# geigerDC3.net
KiCad netlist of a schematic drawn in EAGLE
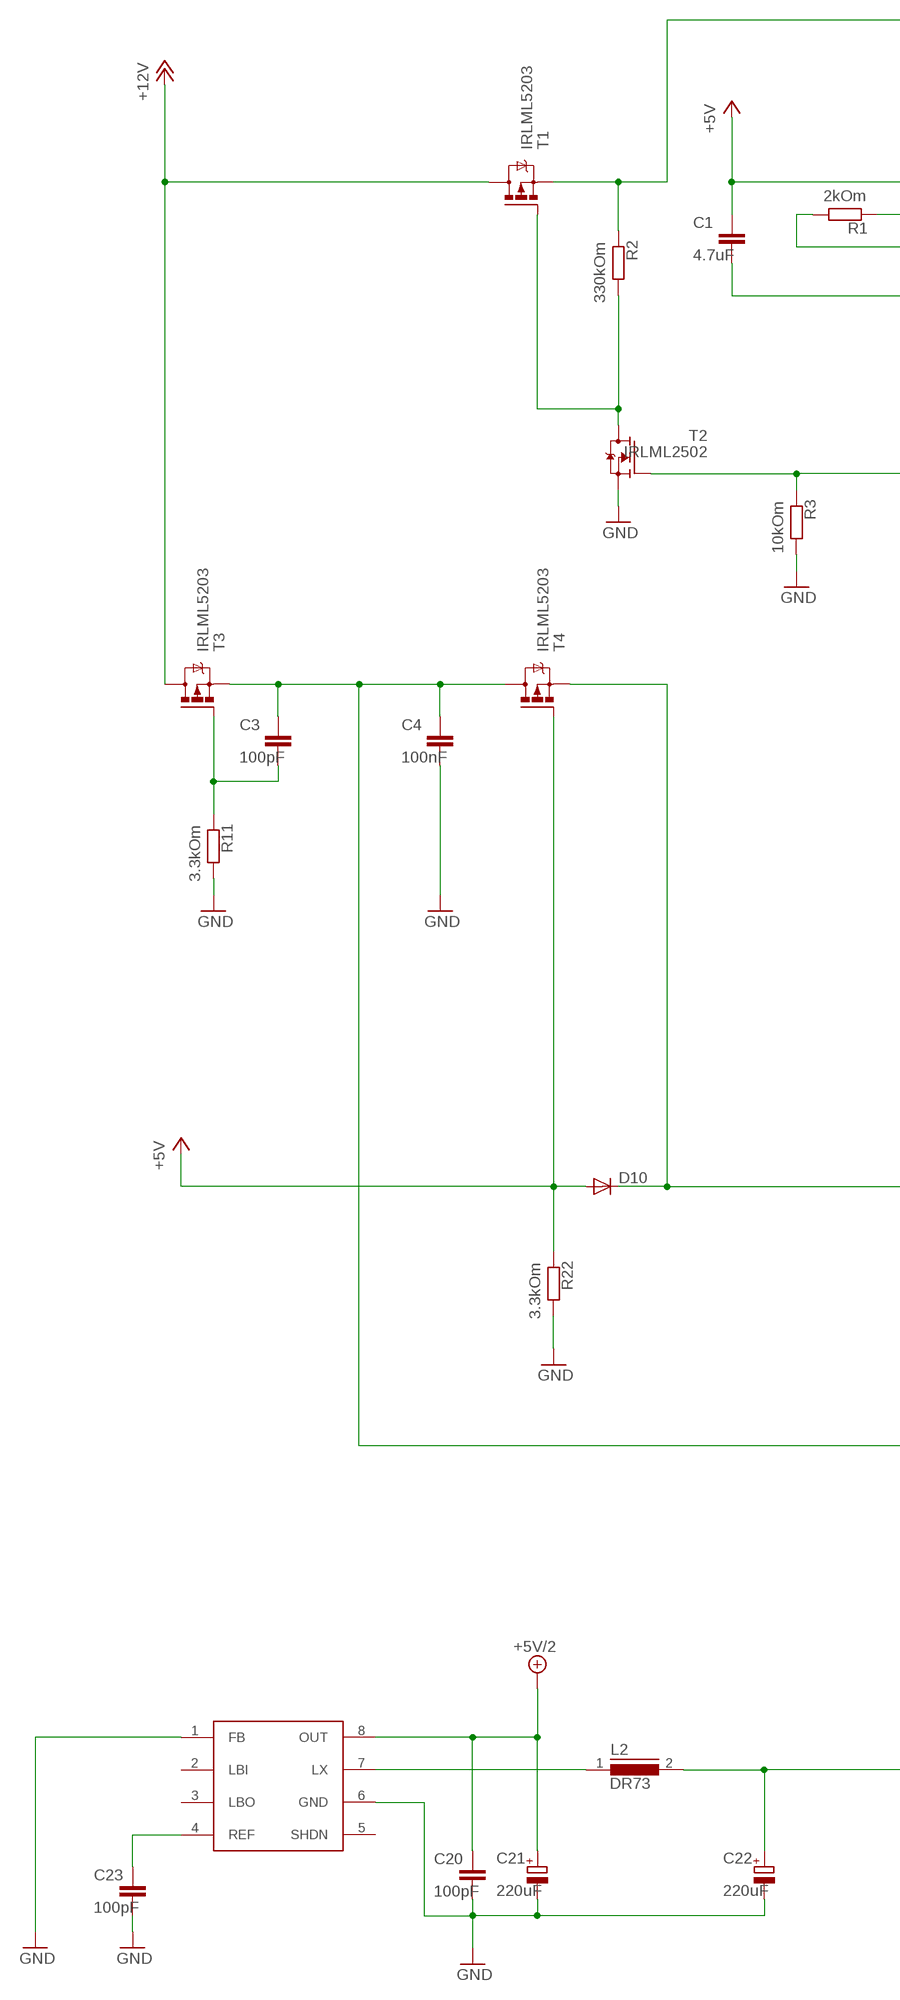
[diagram p0: schematic, sheet 1, part 1 of 3]
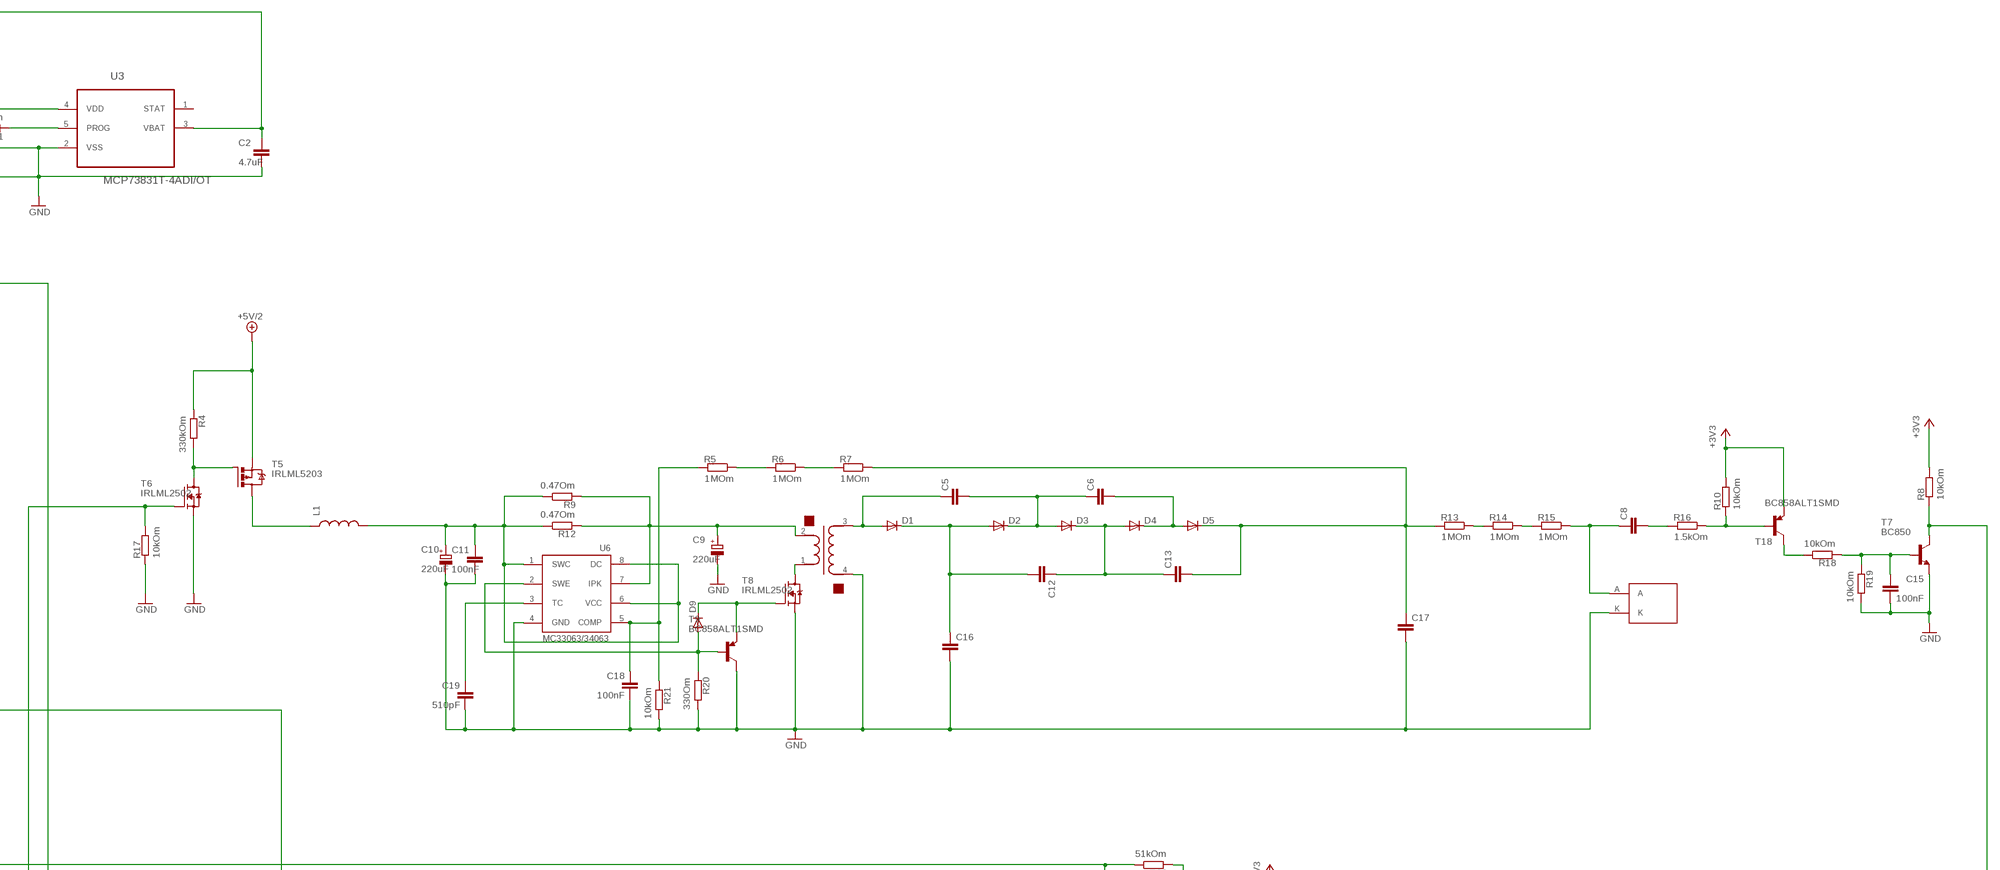
[diagram p1: schematic, sheet 1, part 2 of 3]
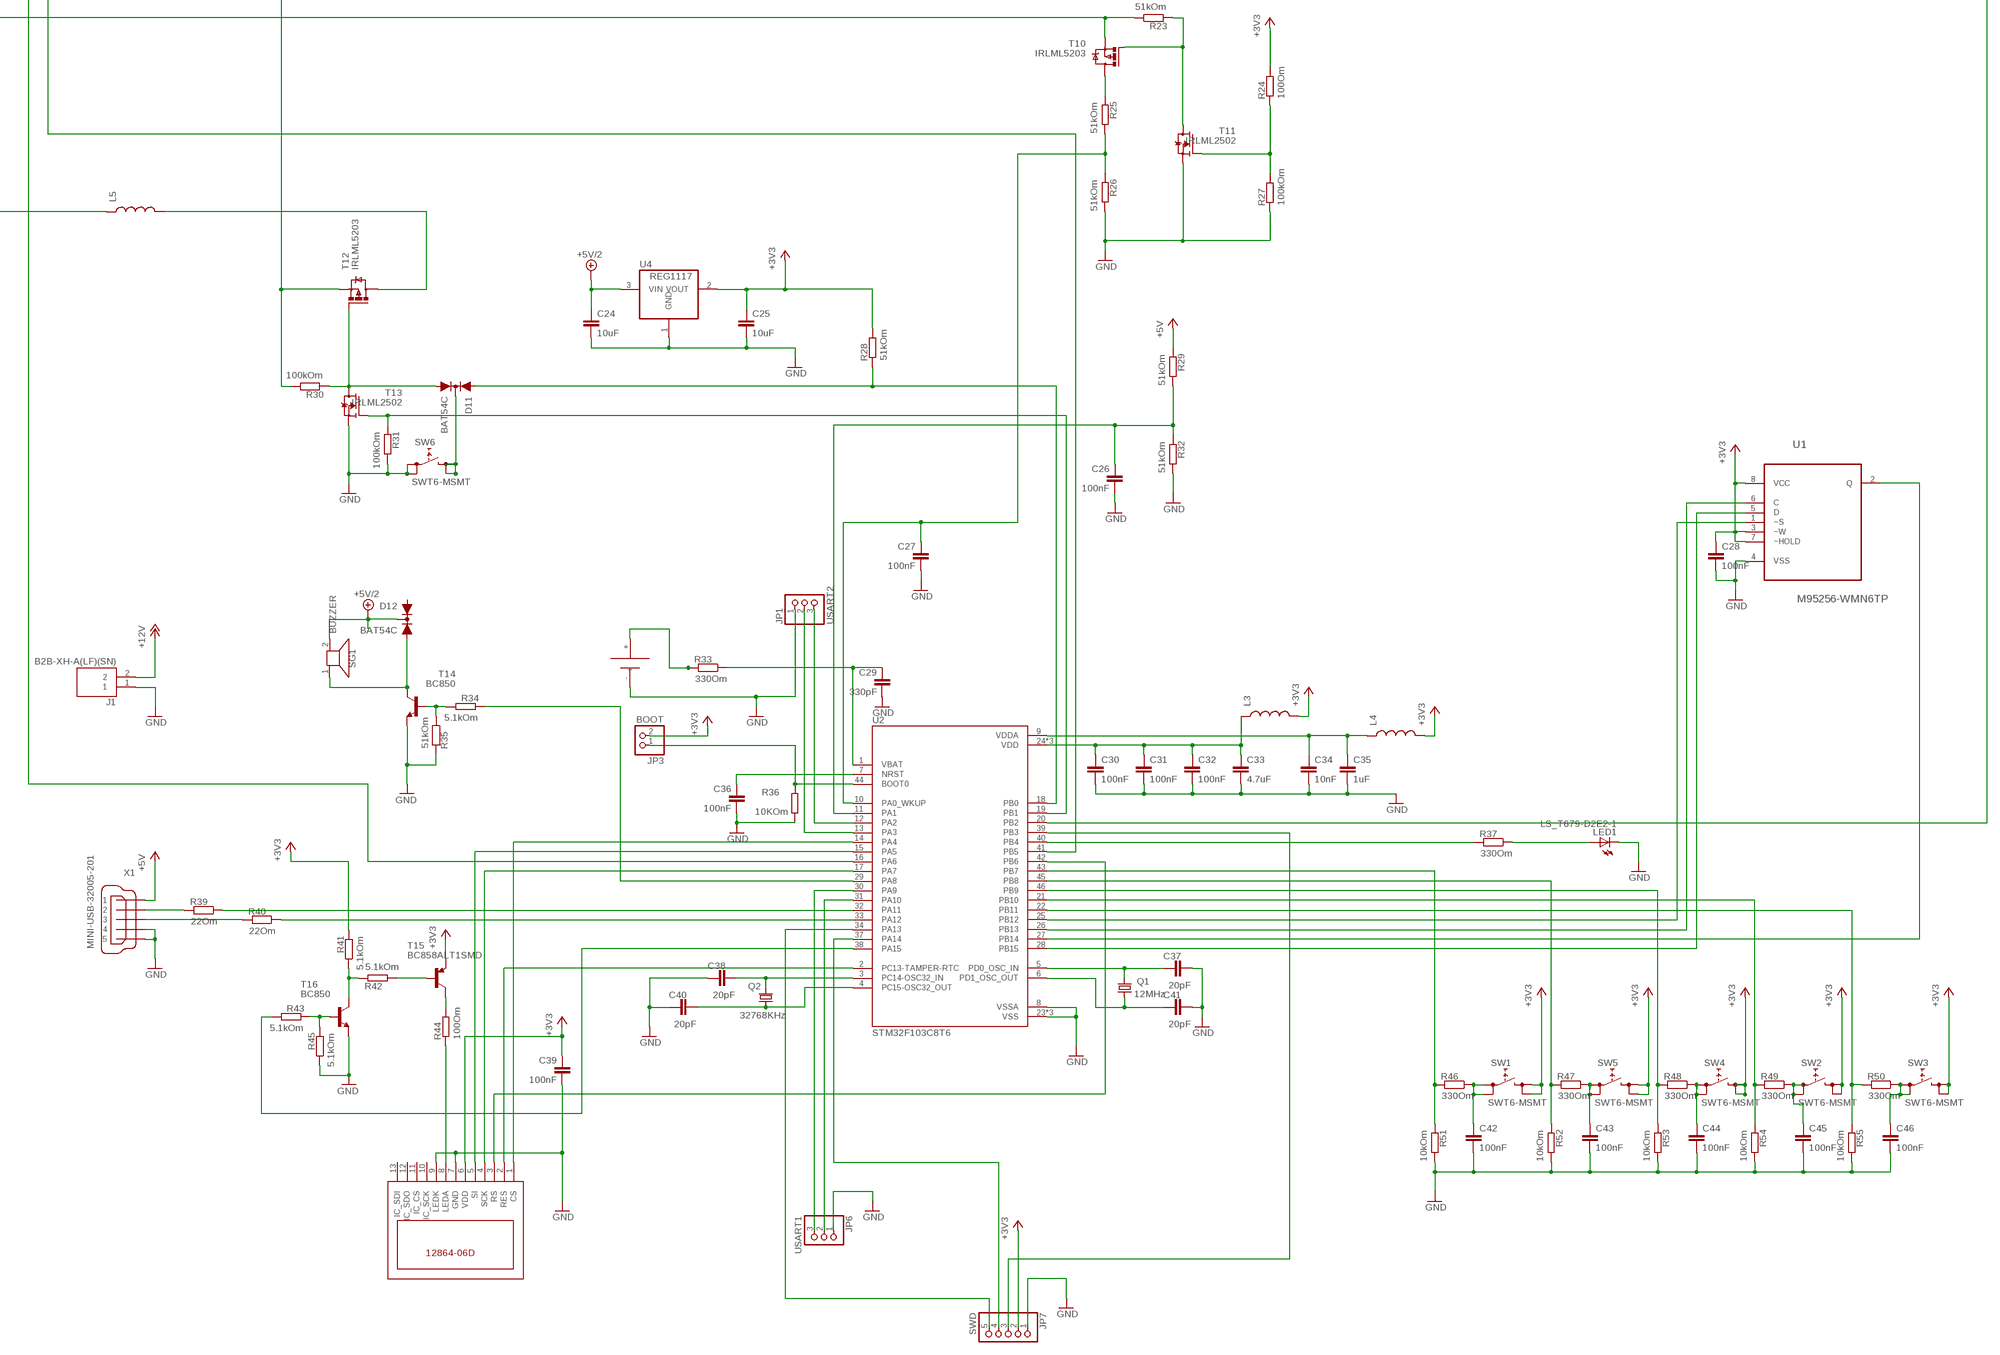
[diagram p2: schematic, sheet 1, part 3 of 3]

(export (version "E")
  (design (tool "Eeschema 10.0.6"))
  (components
    (comp (ref "C1")
      (value "4.7uF")
      (footprint "eagle-import:C0402")
      (libsource (lib "eagle-import") (part "rcl_334_C-EUC0402"))
    )
    (comp (ref "C2")
      (value "4.7uF")
      (footprint "eagle-import:C0402")
      (libsource (lib "eagle-import") (part "rcl_334_C-EUC0402"))
    )
    (comp (ref "C3")
      (value "100pF")
      (footprint "eagle-import:C0402")
      (libsource (lib "eagle-import") (part "rcl_334_C-EUC0402"))
    )
    (comp (ref "C4")
      (value "100nF")
      (footprint "eagle-import:C0402")
      (libsource (lib "eagle-import") (part "rcl_334_C-EUC0402"))
    )
    (comp (ref "C5")
      (value "C-EUC2220K")
      (footprint "eagle-import:C2220K")
      (libsource (lib "eagle-import") (part "C-EUC2220K"))
    )
    (comp (ref "C6")
      (value "C-EUC2220K")
      (footprint "eagle-import:C2220K")
      (libsource (lib "eagle-import") (part "C-EUC2220K"))
    )
    (comp (ref "C8")
      (value "C-EU050-024X044")
      (footprint "eagle-import:C050-024X044")
      (libsource (lib "eagle-import") (part "rcl_334_C-EU050-024X044"))
    )
    (comp (ref "C9")
      (value "220uF")
      (footprint "eagle-import:C_6032-28W")
      (libsource (lib "eagle-import") (part "CPOL-EUC/6032-28W"))
    )
    (comp (ref "C10")
      (value "220uF")
      (footprint "eagle-import:C_6032-28W")
      (libsource (lib "eagle-import") (part "CPOL-EUC/6032-28W"))
    )
    (comp (ref "C11")
      (value "100nF")
      (footprint "eagle-import:C0402")
      (libsource (lib "eagle-import") (part "rcl_334_C-EUC0402"))
    )
    (comp (ref "C12")
      (value "C-EUC2220K")
      (footprint "eagle-import:C2220K")
      (libsource (lib "eagle-import") (part "C-EUC2220K"))
    )
    (comp (ref "C13")
      (value "C-EUC2220K")
      (footprint "eagle-import:C2220K")
      (libsource (lib "eagle-import") (part "C-EUC2220K"))
    )
    (comp (ref "C15")
      (value "100nF")
      (footprint "eagle-import:C0402")
      (libsource (lib "eagle-import") (part "rcl_334_C-EUC0402"))
    )
    (comp (ref "C16")
      (value "C-EUC2220K")
      (footprint "eagle-import:C2220K")
      (libsource (lib "eagle-import") (part "C-EUC2220K"))
    )
    (comp (ref "C17")
      (value "C-EUC2220K")
      (footprint "eagle-import:C2220K")
      (libsource (lib "eagle-import") (part "C-EUC2220K"))
    )
    (comp (ref "C18")
      (value "100nF")
      (footprint "eagle-import:C0402")
      (libsource (lib "eagle-import") (part "rcl_334_C-EUC0402"))
    )
    (comp (ref "C19")
      (value "510pF")
      (footprint "eagle-import:C0402")
      (libsource (lib "eagle-import") (part "rcl_334_C-EUC0402"))
    )
    (comp (ref "C20")
      (value "100pF")
      (footprint "eagle-import:C0402")
      (libsource (lib "eagle-import") (part "rcl_334_C-EUC0402"))
    )
    (comp (ref "C21")
      (value "220uF")
      (footprint "eagle-import:C_6032-28W")
      (libsource (lib "eagle-import") (part "CPOL-EUC/6032-28W"))
    )
    (comp (ref "C22")
      (value "220uF")
      (footprint "eagle-import:C_6032-28W")
      (libsource (lib "eagle-import") (part "CPOL-EUC/6032-28W"))
    )
    (comp (ref "C23")
      (value "100pF")
      (footprint "eagle-import:C0402")
      (libsource (lib "eagle-import") (part "rcl_334_C-EUC0402"))
    )
    (comp (ref "C24")
      (value "10uF")
      (footprint "eagle-import:C0402")
      (libsource (lib "eagle-import") (part "rcl_334_C-EUC0402"))
    )
    (comp (ref "C25")
      (value "10uF")
      (footprint "eagle-import:C0402")
      (libsource (lib "eagle-import") (part "rcl_334_C-EUC0402"))
    )
    (comp (ref "C26")
      (value "100nF")
      (footprint "eagle-import:C0402")
      (libsource (lib "eagle-import") (part "rcl_334_C-EUC0402"))
    )
    (comp (ref "C27")
      (value "100nF")
      (footprint "eagle-import:C0402")
      (libsource (lib "eagle-import") (part "rcl_334_C-EUC0402"))
    )
    (comp (ref "C28")
      (value "100nF")
      (footprint "eagle-import:C0402")
      (libsource (lib "eagle-import") (part "rcl_334_C-EUC0402"))
    )
    (comp (ref "C29")
      (value "330pF")
      (footprint "eagle-import:C0402")
      (libsource (lib "eagle-import") (part "rcl_334_C-EUC0402"))
    )
    (comp (ref "C30")
      (value "100nF")
      (footprint "eagle-import:C0402")
      (libsource (lib "eagle-import") (part "rcl_334_C-EUC0402"))
    )
    (comp (ref "C31")
      (value "100nF")
      (footprint "eagle-import:C0402")
      (libsource (lib "eagle-import") (part "rcl_334_C-EUC0402"))
    )
    (comp (ref "C32")
      (value "100nF")
      (footprint "eagle-import:C0402")
      (libsource (lib "eagle-import") (part "rcl_334_C-EUC0402"))
    )
    (comp (ref "C33")
      (value "4.7uF")
      (footprint "eagle-import:C0402")
      (libsource (lib "eagle-import") (part "rcl_334_C-EUC0402"))
    )
    (comp (ref "C34")
      (value "10nF")
      (footprint "eagle-import:C0402")
      (libsource (lib "eagle-import") (part "rcl_334_C-EUC0402"))
    )
    (comp (ref "C35")
      (value "1uF")
      (footprint "eagle-import:C0402")
      (libsource (lib "eagle-import") (part "rcl_334_C-EUC0402"))
    )
    (comp (ref "C36")
      (value "100nF")
      (footprint "eagle-import:C0402")
      (libsource (lib "eagle-import") (part "rcl_334_C-EUC0402"))
    )
    (comp (ref "C37")
      (value "20pF")
      (footprint "eagle-import:C0402")
      (libsource (lib "eagle-import") (part "rcl_334_C-EUC0402"))
    )
    (comp (ref "C38")
      (value "20pF")
      (footprint "eagle-import:C0402")
      (libsource (lib "eagle-import") (part "rcl_334_C-EUC0402"))
    )
    (comp (ref "C39")
      (value "100nF")
      (footprint "eagle-import:C0402")
      (libsource (lib "eagle-import") (part "rcl_334_C-EUC0402"))
    )
    (comp (ref "C40")
      (value "20pF")
      (footprint "eagle-import:C0402")
      (libsource (lib "eagle-import") (part "rcl_334_C-EUC0402"))
    )
    (comp (ref "C41")
      (value "20pF")
      (footprint "eagle-import:C0402")
      (libsource (lib "eagle-import") (part "rcl_334_C-EUC0402"))
    )
    (comp (ref "C42")
      (value "100nF")
      (footprint "eagle-import:C0402")
      (libsource (lib "eagle-import") (part "rcl_334_C-EUC0402"))
    )
    (comp (ref "C43")
      (value "100nF")
      (footprint "eagle-import:C0402")
      (libsource (lib "eagle-import") (part "rcl_334_C-EUC0402"))
    )
    (comp (ref "C44")
      (value "100nF")
      (footprint "eagle-import:C0402")
      (libsource (lib "eagle-import") (part "rcl_334_C-EUC0402"))
    )
    (comp (ref "C45")
      (value "100nF")
      (footprint "eagle-import:C0402")
      (libsource (lib "eagle-import") (part "rcl_334_C-EUC0402"))
    )
    (comp (ref "C46")
      (value "100nF")
      (footprint "eagle-import:C0402")
      (libsource (lib "eagle-import") (part "rcl_334_C-EUC0402"))
    )
    (comp (ref "D1")
      (value "DIODE-DO214BA")
      (footprint "eagle-import:DO214BA")
      (libsource (lib "eagle-import") (part "DIODE-DO214BA"))
    )
    (comp (ref "D2")
      (value "DIODE-DO214BA")
      (footprint "eagle-import:DO214BA")
      (libsource (lib "eagle-import") (part "DIODE-DO214BA"))
    )
    (comp (ref "D3")
      (value "DIODE-DO214BA")
      (footprint "eagle-import:DO214BA")
      (libsource (lib "eagle-import") (part "DIODE-DO214BA"))
    )
    (comp (ref "D4")
      (value "DIODE-DO214BA")
      (footprint "eagle-import:DO214BA")
      (libsource (lib "eagle-import") (part "DIODE-DO214BA"))
    )
    (comp (ref "D5")
      (value "DIODE-DO214BA")
      (footprint "eagle-import:DO214BA")
      (libsource (lib "eagle-import") (part "DIODE-DO214BA"))
    )
    (comp (ref "D9")
      (value "DIODE-DO-214AC")
      (footprint "eagle-import:DO-214AC")
      (libsource (lib "eagle-import") (part "dp_devices_DIODE-DO-214AC"))
    )
    (comp (ref "D10")
      (value "DIODE-DO-214AC")
      (footprint "eagle-import:DO-214AC")
      (libsource (lib "eagle-import") (part "dp_devices_DIODE-DO-214AC"))
    )
    (comp (ref "D11")
      (value "BAT54C")
      (footprint "eagle-import:SOT23-R")
      (fields (field (name "MF") "ON Semiconductor"))
      (libsource (lib "eagle-import") (part "BAT54C"))
    )
    (comp (ref "D12")
      (value "BAT54C")
      (footprint "eagle-import:SOT23-R")
      (fields (field (name "MF") "ON Semiconductor"))
      (libsource (lib "eagle-import") (part "BAT54C"))
    )
    (comp (ref "J1")
      (value "B2B-XH-A(LF)(SN)")
      (footprint "eagle-import:JST_B2B-XH-A(LF)(SN)")
      (fields (field (name "MF") "JST Sales") (field (name "MP") "B2B-XH-A_LF__SN_"))
      (libsource (lib "eagle-import") (part "B2B-XH-A(LF)(SN)"))
    )
    (comp (ref "JP1")
      (value "USART2")
      (footprint "eagle-import:1X03")
      (libsource (lib "eagle-import") (part "PINHD-1X3"))
    )
    (comp (ref "JP3")
      (value "BOOT")
      (footprint "eagle-import:1X02")
      (libsource (lib "eagle-import") (part "PINHD-1X2"))
    )
    (comp (ref "JP6")
      (value "USART1")
      (footprint "eagle-import:1X03")
      (libsource (lib "eagle-import") (part "PINHD-1X3"))
    )
    (comp (ref "JP7")
      (value "SWD")
      (footprint "eagle-import:1X05")
      (libsource (lib "eagle-import") (part "PINHD-1X5"))
    )
    (comp (ref "L1")
      (value "INDUCTOR0805")
      (footprint "eagle-import:0805")
      (libsource (lib "eagle-import") (part "INDUCTOR0805"))
    )
    (comp (ref "L2")
      (value "DR73")
      (footprint "eagle-import:DR73")
      (libsource (lib "eagle-import") (part "DR73"))
    )
    (comp (ref "L3")
      (value "INDUCTOR0805")
      (footprint "eagle-import:0805")
      (libsource (lib "eagle-import") (part "INDUCTOR0805"))
    )
    (comp (ref "L4")
      (value "INDUCTOR0805")
      (footprint "eagle-import:0805")
      (libsource (lib "eagle-import") (part "INDUCTOR0805"))
    )
    (comp (ref "L5")
      (value "INDUCTOR0805")
      (footprint "eagle-import:0805")
      (libsource (lib "eagle-import") (part "INDUCTOR0805"))
    )
    (comp (ref "LED1")
      (value "LS_T679-D2E2-1")
      (footprint "eagle-import:PLCC2")
      (libsource (lib "eagle-import") (part "_T679-?-1D2E2LS"))
    )
    (comp (ref "Q1")
      (value "12MHz")
      (footprint "eagle-import:HC49UP")
      (libsource (lib "eagle-import") (part "CRYSTALHC49UP"))
    )
    (comp (ref "Q2")
      (value "32768KHz")
      (footprint "eagle-import:8.2X3.8")
      (libsource (lib "eagle-import") (part "KX-327-S"))
    )
    (comp (ref "R1")
      (value "2kOm")
      (footprint "eagle-import:R0402")
      (libsource (lib "eagle-import") (part "rcl_334_R-EU_R0402"))
    )
    (comp (ref "R2")
      (value "330kOm")
      (footprint "eagle-import:R0402")
      (libsource (lib "eagle-import") (part "rcl_334_R-EU_R0402"))
    )
    (comp (ref "R3")
      (value "10kOm")
      (footprint "eagle-import:R0402")
      (libsource (lib "eagle-import") (part "rcl_334_R-EU_R0402"))
    )
    (comp (ref "R4")
      (value "330kOm")
      (footprint "eagle-import:R0402")
      (libsource (lib "eagle-import") (part "rcl_334_R-EU_R0402"))
    )
    (comp (ref "R5")
      (value "1MOm")
      (footprint "eagle-import:R0805")
      (libsource (lib "eagle-import") (part "R-EU_R0805"))
    )
    (comp (ref "R6")
      (value "1MOm")
      (footprint "eagle-import:R0805")
      (libsource (lib "eagle-import") (part "R-EU_R0805"))
    )
    (comp (ref "R7")
      (value "1MOm")
      (footprint "eagle-import:R0805")
      (libsource (lib "eagle-import") (part "R-EU_R0805"))
    )
    (comp (ref "R8")
      (value "10kOm")
      (footprint "eagle-import:R0402")
      (libsource (lib "eagle-import") (part "rcl_334_R-EU_R0402"))
    )
    (comp (ref "R9")
      (value "0.47Om")
      (footprint "eagle-import:R0805")
      (libsource (lib "eagle-import") (part "R-EU_R0805"))
    )
    (comp (ref "R10")
      (value "10kOm")
      (footprint "eagle-import:R0402")
      (libsource (lib "eagle-import") (part "rcl_334_R-EU_R0402"))
    )
    (comp (ref "R11")
      (value "3.3kOm")
      (footprint "eagle-import:R0402")
      (libsource (lib "eagle-import") (part "rcl_334_R-EU_R0402"))
    )
    (comp (ref "R12")
      (value "0.47Om")
      (footprint "eagle-import:R0805")
      (libsource (lib "eagle-import") (part "R-EU_R0805"))
    )
    (comp (ref "R13")
      (value "1MOm")
      (footprint "eagle-import:R0805")
      (libsource (lib "eagle-import") (part "R-EU_R0805"))
    )
    (comp (ref "R14")
      (value "1MOm")
      (footprint "eagle-import:R0805")
      (libsource (lib "eagle-import") (part "R-EU_R0805"))
    )
    (comp (ref "R15")
      (value "1MOm")
      (footprint "eagle-import:R0805")
      (libsource (lib "eagle-import") (part "R-EU_R0805"))
    )
    (comp (ref "R16")
      (value "1.5kOm")
      (footprint "eagle-import:R0402")
      (libsource (lib "eagle-import") (part "rcl_334_R-EU_R0402"))
    )
    (comp (ref "R17")
      (value "10kOm")
      (footprint "eagle-import:R0402")
      (libsource (lib "eagle-import") (part "rcl_334_R-EU_R0402"))
    )
    (comp (ref "R18")
      (value "10kOm")
      (footprint "eagle-import:R0402")
      (libsource (lib "eagle-import") (part "rcl_334_R-EU_R0402"))
    )
    (comp (ref "R19")
      (value "10kOm")
      (footprint "eagle-import:R0402")
      (libsource (lib "eagle-import") (part "rcl_334_R-EU_R0402"))
    )
    (comp (ref "R20")
      (value "330Om")
      (footprint "eagle-import:R0402")
      (libsource (lib "eagle-import") (part "rcl_334_R-EU_R0402"))
    )
    (comp (ref "R21")
      (value "10kOm")
      (footprint "eagle-import:R0805")
      (libsource (lib "eagle-import") (part "R-EU_R0805"))
    )
    (comp (ref "R22")
      (value "3.3kOm")
      (footprint "eagle-import:R0402")
      (libsource (lib "eagle-import") (part "rcl_334_R-EU_R0402"))
    )
    (comp (ref "R23")
      (value "51kOm")
      (footprint "eagle-import:R0402")
      (libsource (lib "eagle-import") (part "rcl_334_R-EU_R0402"))
    )
    (comp (ref "R24")
      (value "100Om")
      (footprint "eagle-import:R0402")
      (libsource (lib "eagle-import") (part "rcl_334_R-EU_R0402"))
    )
    (comp (ref "R25")
      (value "51kOm")
      (footprint "eagle-import:R0402")
      (libsource (lib "eagle-import") (part "rcl_334_R-EU_R0402"))
    )
    (comp (ref "R26")
      (value "51kOm")
      (footprint "eagle-import:R0402")
      (libsource (lib "eagle-import") (part "rcl_334_R-EU_R0402"))
    )
    (comp (ref "R27")
      (value "100kOm")
      (footprint "eagle-import:R0402")
      (libsource (lib "eagle-import") (part "rcl_334_R-EU_R0402"))
    )
    (comp (ref "R28")
      (value "51kOm")
      (footprint "eagle-import:R0402")
      (libsource (lib "eagle-import") (part "rcl_334_R-EU_R0402"))
    )
    (comp (ref "R29")
      (value "51kOm")
      (footprint "eagle-import:R0402")
      (libsource (lib "eagle-import") (part "rcl_334_R-EU_R0402"))
    )
    (comp (ref "R30")
      (value "100kOm")
      (footprint "eagle-import:R0402")
      (libsource (lib "eagle-import") (part "rcl_334_R-EU_R0402"))
    )
    (comp (ref "R31")
      (value "100kOm")
      (footprint "eagle-import:R0402")
      (libsource (lib "eagle-import") (part "rcl_334_R-EU_R0402"))
    )
    (comp (ref "R32")
      (value "51kOm")
      (footprint "eagle-import:R0402")
      (libsource (lib "eagle-import") (part "rcl_334_R-EU_R0402"))
    )
    (comp (ref "R33")
      (value "330Om")
      (footprint "eagle-import:R0402")
      (libsource (lib "eagle-import") (part "rcl_334_R-EU_R0402"))
    )
    (comp (ref "R34")
      (value "5.1kOm")
      (footprint "eagle-import:R0402")
      (libsource (lib "eagle-import") (part "rcl_334_R-EU_R0402"))
    )
    (comp (ref "R35")
      (value "51kOm")
      (footprint "eagle-import:R0402")
      (libsource (lib "eagle-import") (part "rcl_334_R-EU_R0402"))
    )
    (comp (ref "R36")
      (value "10KOm")
      (footprint "eagle-import:R0402")
      (libsource (lib "eagle-import") (part "rcl_334_R-EU_R0402"))
    )
    (comp (ref "R37")
      (value "330Om")
      (footprint "eagle-import:R0402")
      (libsource (lib "eagle-import") (part "rcl_334_R-EU_R0402"))
    )
    (comp (ref "R39")
      (value "22Om")
      (footprint "eagle-import:R0402")
      (libsource (lib "eagle-import") (part "rcl_334_R-EU_R0402"))
    )
    (comp (ref "R40")
      (value "22Om")
      (footprint "eagle-import:R0402")
      (libsource (lib "eagle-import") (part "rcl_334_R-EU_R0402"))
    )
    (comp (ref "R41")
      (value "5.1kOm")
      (footprint "eagle-import:R0402")
      (libsource (lib "eagle-import") (part "rcl_334_R-EU_R0402"))
    )
    (comp (ref "R42")
      (value "5.1kOm")
      (footprint "eagle-import:R0402")
      (libsource (lib "eagle-import") (part "rcl_334_R-EU_R0402"))
    )
    (comp (ref "R43")
      (value "5.1kOm")
      (footprint "eagle-import:R0402")
      (libsource (lib "eagle-import") (part "rcl_334_R-EU_R0402"))
    )
    (comp (ref "R44")
      (value "100Om")
      (footprint "eagle-import:R0805")
      (libsource (lib "eagle-import") (part "R-EU_R0805"))
    )
    (comp (ref "R45")
      (value "5.1kOm")
      (footprint "eagle-import:R0402")
      (libsource (lib "eagle-import") (part "rcl_334_R-EU_R0402"))
    )
    (comp (ref "R46")
      (value "330Om")
      (footprint "eagle-import:R0402")
      (libsource (lib "eagle-import") (part "rcl_334_R-EU_R0402"))
    )
    (comp (ref "R47")
      (value "330Om")
      (footprint "eagle-import:R0402")
      (libsource (lib "eagle-import") (part "rcl_334_R-EU_R0402"))
    )
    (comp (ref "R48")
      (value "330Om")
      (footprint "eagle-import:R0402")
      (libsource (lib "eagle-import") (part "rcl_334_R-EU_R0402"))
    )
    (comp (ref "R49")
      (value "330Om")
      (footprint "eagle-import:R0402")
      (libsource (lib "eagle-import") (part "rcl_334_R-EU_R0402"))
    )
    (comp (ref "R50")
      (value "330Om")
      (footprint "eagle-import:R0402")
      (libsource (lib "eagle-import") (part "rcl_334_R-EU_R0402"))
    )
    (comp (ref "R51")
      (value "10kOm")
      (footprint "eagle-import:R0402")
      (libsource (lib "eagle-import") (part "rcl_334_R-EU_R0402"))
    )
    (comp (ref "R52")
      (value "10kOm")
      (footprint "eagle-import:R0402")
      (libsource (lib "eagle-import") (part "rcl_334_R-EU_R0402"))
    )
    (comp (ref "R53")
      (value "10kOm")
      (footprint "eagle-import:R0402")
      (libsource (lib "eagle-import") (part "rcl_334_R-EU_R0402"))
    )
    (comp (ref "R54")
      (value "10kOm")
      (footprint "eagle-import:R0402")
      (libsource (lib "eagle-import") (part "rcl_334_R-EU_R0402"))
    )
    (comp (ref "R55")
      (value "10kOm")
      (footprint "eagle-import:R0402")
      (libsource (lib "eagle-import") (part "rcl_334_R-EU_R0402"))
    )
    (comp (ref "SG1")
      (value "BUZZER")
      (footprint "eagle-import:BUZZER")
      (libsource (lib "eagle-import") (part "BUZZER"))
    )
    (comp (ref "SW1")
      (value "SWT6-MSMT")
      (footprint "eagle-import:SWT6-M")
      (libsource (lib "eagle-import") (part "SWT6-MSMT"))
    )
    (comp (ref "SW2")
      (value "SWT6-MSMT")
      (footprint "eagle-import:SWT6-M")
      (libsource (lib "eagle-import") (part "SWT6-MSMT"))
    )
    (comp (ref "SW3")
      (value "SWT6-MSMT")
      (footprint "eagle-import:SWT6-M")
      (libsource (lib "eagle-import") (part "SWT6-MSMT"))
    )
    (comp (ref "SW4")
      (value "SWT6-MSMT")
      (footprint "eagle-import:SWT6-M")
      (libsource (lib "eagle-import") (part "SWT6-MSMT"))
    )
    (comp (ref "SW5")
      (value "SWT6-MSMT")
      (footprint "eagle-import:SWT6-M")
      (libsource (lib "eagle-import") (part "SWT6-MSMT"))
    )
    (comp (ref "SW6")
      (value "SWT6-MSMT")
      (footprint "eagle-import:SWT6-M")
      (libsource (lib "eagle-import") (part "SWT6-MSMT"))
    )
    (comp (ref "T1")
      (value "IRLML5203")
      (footprint "eagle-import:MICRO3")
      (libsource (lib "eagle-import") (part "IRLML5203"))
    )
    (comp (ref "T2")
      (value "IRLML2502")
      (footprint "eagle-import:SOT23")
      (fields (field (name "MF") "Infineon Technologies"))
      (libsource (lib "eagle-import") (part "IRLML2502"))
    )
    (comp (ref "T3")
      (value "IRLML5203")
      (footprint "eagle-import:MICRO3")
      (libsource (lib "eagle-import") (part "IRLML5203"))
    )
    (comp (ref "T4")
      (value "IRLML5203")
      (footprint "eagle-import:MICRO3")
      (libsource (lib "eagle-import") (part "IRLML5203"))
    )
    (comp (ref "T5")
      (value "IRLML5203")
      (footprint "eagle-import:MICRO3")
      (libsource (lib "eagle-import") (part "IRLML5203"))
    )
    (comp (ref "T6")
      (value "IRLML2502")
      (footprint "eagle-import:SOT23")
      (fields (field (name "MF") "Infineon Technologies"))
      (libsource (lib "eagle-import") (part "IRLML2502"))
    )
    (comp (ref "T7")
      (value "BC850")
      (footprint "eagle-import:SOT23")
      (libsource (lib "eagle-import") (part "BC850"))
    )
    (comp (ref "T8")
      (value "IRLML2502")
      (footprint "eagle-import:SOT23")
      (fields (field (name "MF") "Infineon Technologies"))
      (libsource (lib "eagle-import") (part "IRLML2502"))
    )
    (comp (ref "T9")
      (value "BC858ALT1SMD")
      (footprint "eagle-import:SOT23-BEC")
      (libsource (lib "eagle-import") (part "BC858SMDALT1"))
    )
    (comp (ref "T10")
      (value "IRLML5203")
      (footprint "eagle-import:MICRO3")
      (libsource (lib "eagle-import") (part "IRLML5203"))
    )
    (comp (ref "T11")
      (value "IRLML2502")
      (footprint "eagle-import:SOT23")
      (fields (field (name "MF") "Infineon Technologies"))
      (libsource (lib "eagle-import") (part "IRLML2502"))
    )
    (comp (ref "T12")
      (value "IRLML5203")
      (footprint "eagle-import:MICRO3")
      (libsource (lib "eagle-import") (part "IRLML5203"))
    )
    (comp (ref "T13")
      (value "IRLML2502")
      (footprint "eagle-import:SOT23")
      (fields (field (name "MF") "Infineon Technologies"))
      (libsource (lib "eagle-import") (part "IRLML2502"))
    )
    (comp (ref "T14")
      (value "BC850")
      (footprint "eagle-import:SOT23")
      (libsource (lib "eagle-import") (part "BC850"))
    )
    (comp (ref "T15")
      (value "BC858ALT1SMD")
      (footprint "eagle-import:SOT23-BEC")
      (libsource (lib "eagle-import") (part "BC858SMDALT1"))
    )
    (comp (ref "T16")
      (value "BC850")
      (footprint "eagle-import:SOT23")
      (libsource (lib "eagle-import") (part "BC850"))
    )
    (comp (ref "T18")
      (value "BC858ALT1SMD")
      (footprint "eagle-import:SOT23-BEC")
      (libsource (lib "eagle-import") (part "BC858SMDALT1"))
    )
    (comp (ref "TR1")
      (value "TRANSFORMER")
      (footprint "eagle-import:TRANSFORMER")
      (libsource (lib "eagle-import") (part "TRANSFORMER"))
    )
    (comp (ref "TUBE")
      (value "TUBE")
      (footprint "eagle-import:XH-B3B")
      (libsource (lib "eagle-import") (part "TUBE"))
    )
    (comp (ref "U$1")
      (value "DS1092-10-W6L")
      (footprint "eagle-import:DS1092-10-W6L")
      (libsource (lib "eagle-import") (part "DS1092-10-W6L"))
    )
    (comp (ref "U$5")
      (value "12864-06D")
      (footprint "eagle-import:12864-06D")
      (libsource (lib "eagle-import") (part "12864-06D"))
    )
    (comp (ref "U1")
      (value "M95256-WMN6TP")
      (footprint "eagle-import:SOIC127P600X175-8N")
      (fields (field (name "MF") "STMicroelectronics"))
      (libsource (lib "eagle-import") (part "M95256-WMN6TP"))
    )
    (comp (ref "U2")
      (value "STM32F103C8T6")
      (footprint "eagle-import:QFP50P900X900X160-48N")
      (fields (field (name "MF") "STMicroelectronics"))
      (libsource (lib "eagle-import") (part "STM32F103C8T6"))
    )
    (comp (ref "U3")
      (value "MCP73831T-4ADI/OT")
      (footprint "eagle-import:SOT95P280X145-5N")
      (fields (field (name "MF") "Microchip"))
      (libsource (lib "eagle-import") (part "MCP73831T-4ADI/OT"))
    )
    (comp (ref "U4")
      (value "REG1117")
      (footprint "eagle-import:SOT223")
      (libsource (lib "eagle-import") (part "REG1117"))
    )
    (comp (ref "U5")
      (value "L6920DTR")
      (footprint "eagle-import:TSSOP8")
      (libsource (lib "eagle-import") (part "L6920DTR"))
    )
    (comp (ref "U6")
      (value "MC33063/MC34063D")
      (footprint "eagle-import:SO08")
      (libsource (lib "eagle-import") (part "MC33063/MC34063D"))
    )
    (comp (ref "X1")
      (value "MINI-USB-32005-201")
      (footprint "eagle-import:32005-201")
      (libsource (lib "eagle-import") (part "MINI-USB-32005-201"))
    )
  )
  (nets
    (net (code "1") (name "+3V3") (class "Default")
      (node (ref "C25") (pin "1") (pinfunction "1_1") (pintype "passive"))
      (node (ref "C28") (pin "1") (pinfunction "1_1") (pintype "passive"))
      (node (ref "C39") (pin "1") (pinfunction "1_1") (pintype "passive"))
      (node (ref "JP3") (pin "2") (pinfunction "2_2") (pintype "passive"))
      (node (ref "JP7") (pin "2") (pinfunction "2_2") (pintype "passive"))
      (node (ref "L3") (pin "2") (pinfunction "2_2") (pintype "passive"))
      (node (ref "L4") (pin "2") (pinfunction "2_2") (pintype "passive"))
      (node (ref "R10") (pin "1") (pinfunction "1_1") (pintype "passive"))
      (node (ref "R24") (pin "1") (pinfunction "1_1") (pintype "passive"))
      (node (ref "R28") (pin "1") (pinfunction "1_1") (pintype "passive"))
      (node (ref "R41") (pin "2") (pinfunction "2_2") (pintype "passive"))
      (node (ref "R8") (pin "1") (pinfunction "1_1") (pintype "passive"))
      (node (ref "SW1") (pin "3") (pinfunction "1_3") (pintype "passive"))
      (node (ref "SW1") (pin "4") (pinfunction "1_4") (pintype "passive"))
      (node (ref "SW2") (pin "3") (pinfunction "1_3") (pintype "passive"))
      (node (ref "SW2") (pin "4") (pinfunction "1_4") (pintype "passive"))
      (node (ref "SW3") (pin "3") (pinfunction "1_3") (pintype "passive"))
      (node (ref "SW3") (pin "4") (pinfunction "1_4") (pintype "passive"))
      (node (ref "SW4") (pin "3") (pinfunction "1_3") (pintype "passive"))
      (node (ref "SW4") (pin "4") (pinfunction "1_4") (pintype "passive"))
      (node (ref "SW5") (pin "3") (pinfunction "1_3") (pintype "passive"))
      (node (ref "SW5") (pin "4") (pinfunction "1_4") (pintype "passive"))
      (node (ref "T15") (pin "E") (pinfunction "E_E") (pintype "passive"))
      (node (ref "T18") (pin "E") (pinfunction "E_E") (pintype "passive"))
      (node (ref "U$5") (pin "6") (pinfunction "VDD_6") (pintype "bidirectional"))
      (node (ref "U1") (pin "3") (pinfunction "~{W}_3") (pintype "input"))
      (node (ref "U1") (pin "7") (pinfunction "~{HOLD}_7") (pintype "input"))
      (node (ref "U1") (pin "8") (pinfunction "VCC_8") (pintype "power_in"))
      (node (ref "U4") (pin "2") (pinfunction "VOUT_2") (pintype "output"))
    )
    (net (code "2") (name "+5V") (class "Default")
      (node (ref "C1") (pin "1") (pinfunction "1_1") (pintype "passive"))
      (node (ref "D10") (pin "2") (pinfunction "A_2") (pintype "passive"))
      (node (ref "R22") (pin "2") (pinfunction "2_2") (pintype "passive"))
      (node (ref "R29") (pin "2") (pinfunction "2_2") (pintype "passive"))
      (node (ref "T4") (pin "1") (pinfunction "G_1") (pintype "passive"))
      (node (ref "U3") (pin "4") (pinfunction "VDD_4") (pintype "power_in"))
      (node (ref "X1") (pin "1") (pinfunction "1_1") (pintype "passive"))
    )
    (net (code "3") (name "+5V{slash}2") (class "Default")
      (node (ref "C20") (pin "1") (pinfunction "1_1") (pintype "passive"))
      (node (ref "C21") (pin "+") (pinfunction "+_+") (pintype "passive"))
      (node (ref "C24") (pin "1") (pinfunction "1_1") (pintype "passive"))
      (node (ref "D12") (pin "3") (pinfunction "C_3") (pintype "passive"))
      (node (ref "R4") (pin "2") (pinfunction "2_2") (pintype "passive"))
      (node (ref "SG1") (pin "2") (pinfunction "2_2") (pintype "passive"))
      (node (ref "T5") (pin "2") (pinfunction "S_2") (pintype "passive"))
      (node (ref "U4") (pin "3") (pinfunction "VIN_3") (pintype "input"))
      (node (ref "U5") (pin "8") (pinfunction "OUT_8") (pintype "bidirectional"))
    )
    (net (code "4") (name "+12V") (class "Default")
      (node (ref "J1") (pin "2") (pinfunction "2_2") (pintype "passive"))
      (node (ref "T1") (pin "3") (pinfunction "D_3") (pintype "passive"))
      (node (ref "T3") (pin "3") (pinfunction "D_3") (pintype "passive"))
    )
    (net (code "5") (name "GND") (class "Default")
      (node (ref "C1") (pin "2") (pinfunction "2_2") (pintype "passive"))
      (node (ref "C10") (pin "-") (pinfunction "-_-") (pintype "passive"))
      (node (ref "C11") (pin "2") (pinfunction "2_2") (pintype "passive"))
      (node (ref "C15") (pin "2") (pinfunction "2_2") (pintype "passive"))
      (node (ref "C16") (pin "2") (pinfunction "2_2") (pintype "passive"))
      (node (ref "C17") (pin "2") (pinfunction "2_2") (pintype "passive"))
      (node (ref "C18") (pin "2") (pinfunction "2_2") (pintype "passive"))
      (node (ref "C19") (pin "2") (pinfunction "2_2") (pintype "passive"))
      (node (ref "C2") (pin "2") (pinfunction "2_2") (pintype "passive"))
      (node (ref "C20") (pin "2") (pinfunction "2_2") (pintype "passive"))
      (node (ref "C21") (pin "-") (pinfunction "-_-") (pintype "passive"))
      (node (ref "C22") (pin "-") (pinfunction "-_-") (pintype "passive"))
      (node (ref "C23") (pin "2") (pinfunction "2_2") (pintype "passive"))
      (node (ref "C24") (pin "2") (pinfunction "2_2") (pintype "passive"))
      (node (ref "C25") (pin "2") (pinfunction "2_2") (pintype "passive"))
      (node (ref "C26") (pin "2") (pinfunction "2_2") (pintype "passive"))
      (node (ref "C27") (pin "2") (pinfunction "2_2") (pintype "passive"))
      (node (ref "C28") (pin "2") (pinfunction "2_2") (pintype "passive"))
      (node (ref "C29") (pin "2") (pinfunction "2_2") (pintype "passive"))
      (node (ref "C30") (pin "2") (pinfunction "2_2") (pintype "passive"))
      (node (ref "C31") (pin "2") (pinfunction "2_2") (pintype "passive"))
      (node (ref "C32") (pin "2") (pinfunction "2_2") (pintype "passive"))
      (node (ref "C33") (pin "2") (pinfunction "2_2") (pintype "passive"))
      (node (ref "C34") (pin "2") (pinfunction "2_2") (pintype "passive"))
      (node (ref "C35") (pin "2") (pinfunction "2_2") (pintype "passive"))
      (node (ref "C36") (pin "2") (pinfunction "2_2") (pintype "passive"))
      (node (ref "C37") (pin "2") (pinfunction "2_2") (pintype "passive"))
      (node (ref "C38") (pin "1") (pinfunction "1_1") (pintype "passive"))
      (node (ref "C39") (pin "2") (pinfunction "2_2") (pintype "passive"))
      (node (ref "C4") (pin "2") (pinfunction "2_2") (pintype "passive"))
      (node (ref "C40") (pin "1") (pinfunction "1_1") (pintype "passive"))
      (node (ref "C41") (pin "2") (pinfunction "2_2") (pintype "passive"))
      (node (ref "C42") (pin "2") (pinfunction "2_2") (pintype "passive"))
      (node (ref "C43") (pin "2") (pinfunction "2_2") (pintype "passive"))
      (node (ref "C44") (pin "2") (pinfunction "2_2") (pintype "passive"))
      (node (ref "C45") (pin "2") (pinfunction "2_2") (pintype "passive"))
      (node (ref "C46") (pin "2") (pinfunction "2_2") (pintype "passive"))
      (node (ref "C9") (pin "-") (pinfunction "-_-") (pintype "passive"))
      (node (ref "J1") (pin "1") (pinfunction "1_1") (pintype "passive"))
      (node (ref "JP1") (pin "1") (pinfunction "1_1") (pintype "passive"))
      (node (ref "JP6") (pin "1") (pinfunction "1_1") (pintype "passive"))
      (node (ref "JP7") (pin "1") (pinfunction "1_1") (pintype "passive"))
      (node (ref "LED1") (pin "C") (pinfunction "C_C") (pintype "passive"))
      (node (ref "R1") (pin "1") (pinfunction "1_1") (pintype "passive"))
      (node (ref "R11") (pin "1") (pinfunction "1_1") (pintype "passive"))
      (node (ref "R17") (pin "2") (pinfunction "2_2") (pintype "passive"))
      (node (ref "R19") (pin "1") (pinfunction "1_1") (pintype "passive"))
      (node (ref "R20") (pin "1") (pinfunction "1_1") (pintype "passive"))
      (node (ref "R21") (pin "1") (pinfunction "1_1") (pintype "passive"))
      (node (ref "R22") (pin "1") (pinfunction "1_1") (pintype "passive"))
      (node (ref "R26") (pin "1") (pinfunction "1_1") (pintype "passive"))
      (node (ref "R27") (pin "2") (pinfunction "2_2") (pintype "passive"))
      (node (ref "R3") (pin "1") (pinfunction "1_1") (pintype "passive"))
      (node (ref "R31") (pin "1") (pinfunction "1_1") (pintype "passive"))
      (node (ref "R32") (pin "1") (pinfunction "1_1") (pintype "passive"))
      (node (ref "R35") (pin "2") (pinfunction "2_2") (pintype "passive"))
      (node (ref "R36") (pin "1") (pinfunction "1_1") (pintype "passive"))
      (node (ref "R45") (pin "1") (pinfunction "1_1") (pintype "passive"))
      (node (ref "R51") (pin "1") (pinfunction "1_1") (pintype "passive"))
      (node (ref "R52") (pin "1") (pinfunction "1_1") (pintype "passive"))
      (node (ref "R53") (pin "1") (pinfunction "1_1") (pintype "passive"))
      (node (ref "R54") (pin "1") (pinfunction "1_1") (pintype "passive"))
      (node (ref "R55") (pin "1") (pinfunction "1_1") (pintype "passive"))
      (node (ref "SW6") (pin "1") (pinfunction "0_1") (pintype "passive"))
      (node (ref "SW6") (pin "2") (pinfunction "0_2") (pintype "passive"))
      (node (ref "T11") (pin "2") (pinfunction "S_2") (pintype "passive"))
      (node (ref "T13") (pin "2") (pinfunction "S_2") (pintype "passive"))
      (node (ref "T14") (pin "2") (pinfunction "E_2") (pintype "passive"))
      (node (ref "T16") (pin "2") (pinfunction "E_2") (pintype "passive"))
      (node (ref "T2") (pin "2") (pinfunction "S_2") (pintype "passive"))
      (node (ref "T6") (pin "2") (pinfunction "S_2") (pintype "passive"))
      (node (ref "T7") (pin "2") (pinfunction "E_2") (pintype "passive"))
      (node (ref "T8") (pin "2") (pinfunction "S_2") (pintype "passive"))
      (node (ref "T9") (pin "C") (pinfunction "C_C") (pintype "passive"))
      (node (ref "TR1") (pin "4") (pinfunction "4_4") (pintype "bidirectional"))
      (node (ref "TUBE") (pin "K") (pinfunction "K_K") (pintype "bidirectional"))
      (node (ref "U$1") (pin "-") (pinfunction "-_-") (pintype "bidirectional"))
      (node (ref "U$5") (pin "7") (pinfunction "GND_7") (pintype "bidirectional"))
      (node (ref "U$5") (pin "9") (pinfunction "LEDK_9") (pintype "bidirectional"))
      (node (ref "U1") (pin "4") (pinfunction "VSS_4") (pintype "power_in"))
      (node (ref "U2") (pin "23") (pinfunction "VSS_23") (pintype "power_in"))
      (node (ref "U2") (pin "35") (pinfunction "VSS_35") (pintype "power_in"))
      (node (ref "U2") (pin "47") (pinfunction "VSS_47") (pintype "power_in"))
      (node (ref "U2") (pin "8") (pinfunction "VSSA_8") (pintype "power_in"))
      (node (ref "U3") (pin "2") (pinfunction "VSS_2") (pintype "power_in"))
      (node (ref "U4") (pin "1") (pinfunction "GND_1") (pintype "power_in"))
      (node (ref "U5") (pin "1") (pinfunction "FB_1") (pintype "bidirectional"))
      (node (ref "U5") (pin "6") (pinfunction "GND_6") (pintype "bidirectional"))
      (node (ref "U6") (pin "4") (pinfunction "GND_4") (pintype "power_in"))
      (node (ref "X1") (pin "4") (pinfunction "4_4") (pintype "passive"))
      (node (ref "X1") (pin "5") (pinfunction "5_5") (pintype "passive"))
    )
    (net (code "6") (name "Net-(C5-Pad1)") (class "Default")
      (node (ref "C5") (pin "1") (pinfunction "1_1") (pintype "passive"))
      (node (ref "D1") (pin "A") (pinfunction "A_A") (pintype "passive"))
      (node (ref "TR1") (pin "3") (pinfunction "3_3") (pintype "bidirectional"))
    )
    (net (code "7") (name "Net-(C5-Pad2)") (class "Default")
      (node (ref "C5") (pin "2") (pinfunction "2_2") (pintype "passive"))
      (node (ref "C6") (pin "1") (pinfunction "1_1") (pintype "passive"))
      (node (ref "D2") (pin "C") (pinfunction "C_C") (pintype "passive"))
      (node (ref "D3") (pin "A") (pinfunction "A_A") (pintype "passive"))
    )
    (net (code "8") (name "Net-(C6-Pad2)") (class "Default")
      (node (ref "C6") (pin "2") (pinfunction "2_2") (pintype "passive"))
      (node (ref "D4") (pin "C") (pinfunction "C_C") (pintype "passive"))
      (node (ref "D5") (pin "A") (pinfunction "A_A") (pintype "passive"))
    )
    (net (code "9") (name "Net-(C8-Pad1)") (class "Default")
      (node (ref "C8") (pin "1") (pinfunction "1_1") (pintype "passive"))
      (node (ref "R15") (pin "1") (pinfunction "1_1") (pintype "passive"))
      (node (ref "TUBE") (pin "A") (pinfunction "A_A") (pintype "bidirectional"))
    )
    (net (code "10") (name "Net-(C8-Pad2)") (class "Default")
      (node (ref "C8") (pin "2") (pinfunction "2_2") (pintype "passive"))
      (node (ref "R16") (pin "2") (pinfunction "2_2") (pintype "passive"))
    )
    (net (code "11") (name "Net-(C12-Pad1)") (class "Default")
      (node (ref "C12") (pin "1") (pinfunction "1_1") (pintype "passive"))
      (node (ref "C13") (pin "1") (pinfunction "1_1") (pintype "passive"))
      (node (ref "D3") (pin "C") (pinfunction "C_C") (pintype "passive"))
      (node (ref "D4") (pin "A") (pinfunction "A_A") (pintype "passive"))
    )
    (net (code "12") (name "Net-(C12-Pad2)") (class "Default")
      (node (ref "C12") (pin "2") (pinfunction "2_2") (pintype "passive"))
      (node (ref "C16") (pin "1") (pinfunction "1_1") (pintype "passive"))
      (node (ref "D1") (pin "C") (pinfunction "C_C") (pintype "passive"))
      (node (ref "D2") (pin "A") (pinfunction "A_A") (pintype "passive"))
    )
    (net (code "13") (name "Net-(C13-Pad2)") (class "Default")
      (node (ref "C13") (pin "2") (pinfunction "2_2") (pintype "passive"))
      (node (ref "C17") (pin "1") (pinfunction "1_1") (pintype "passive"))
      (node (ref "D5") (pin "C") (pinfunction "C_C") (pintype "passive"))
      (node (ref "R13") (pin "2") (pinfunction "2_2") (pintype "passive"))
      (node (ref "R7") (pin "1") (pinfunction "1_1") (pintype "passive"))
    )
    (net (code "14") (name "Net-(C22-Pad+)") (class "Default")
      (node (ref "C22") (pin "+") (pinfunction "+_+") (pintype "passive"))
      (node (ref "L2") (pin "2") (pinfunction "2_2") (pintype "passive"))
      (node (ref "L5") (pin "1") (pinfunction "1_1") (pintype "passive"))
    )
    (net (code "15") (name "Net-(C30-Pad1)") (class "Default")
      (node (ref "C30") (pin "1") (pinfunction "1_1") (pintype "passive"))
      (node (ref "C31") (pin "1") (pinfunction "1_1") (pintype "passive"))
      (node (ref "C32") (pin "1") (pinfunction "1_1") (pintype "passive"))
      (node (ref "C33") (pin "1") (pinfunction "1_1") (pintype "passive"))
      (node (ref "L3") (pin "1") (pinfunction "1_1") (pintype "passive"))
      (node (ref "U2") (pin "24") (pinfunction "VDD_24") (pintype "power_in"))
      (node (ref "U2") (pin "36") (pinfunction "VDD_36") (pintype "power_in"))
      (node (ref "U2") (pin "48") (pinfunction "VDD_48") (pintype "power_in"))
    )
    (net (code "16") (name "Net-(C42-Pad1)") (class "Default")
      (node (ref "C42") (pin "1") (pinfunction "1_1") (pintype "passive"))
      (node (ref "R46") (pin "1") (pinfunction "1_1") (pintype "passive"))
      (node (ref "SW1") (pin "1") (pinfunction "0_1") (pintype "passive"))
      (node (ref "SW1") (pin "2") (pinfunction "0_2") (pintype "passive"))
    )
    (net (code "17") (name "Net-(C43-Pad1)") (class "Default")
      (node (ref "C43") (pin "1") (pinfunction "1_1") (pintype "passive"))
      (node (ref "R47") (pin "1") (pinfunction "1_1") (pintype "passive"))
      (node (ref "SW5") (pin "1") (pinfunction "0_1") (pintype "passive"))
      (node (ref "SW5") (pin "2") (pinfunction "0_2") (pintype "passive"))
    )
    (net (code "18") (name "Net-(C44-Pad1)") (class "Default")
      (node (ref "C44") (pin "1") (pinfunction "1_1") (pintype "passive"))
      (node (ref "R48") (pin "1") (pinfunction "1_1") (pintype "passive"))
      (node (ref "SW4") (pin "1") (pinfunction "0_1") (pintype "passive"))
      (node (ref "SW4") (pin "2") (pinfunction "0_2") (pintype "passive"))
    )
    (net (code "19") (name "Net-(C45-Pad1)") (class "Default")
      (node (ref "C45") (pin "1") (pinfunction "1_1") (pintype "passive"))
      (node (ref "R49") (pin "1") (pinfunction "1_1") (pintype "passive"))
      (node (ref "SW2") (pin "1") (pinfunction "0_1") (pintype "passive"))
      (node (ref "SW2") (pin "2") (pinfunction "0_2") (pintype "passive"))
    )
    (net (code "20") (name "Net-(C46-Pad1)") (class "Default")
      (node (ref "C46") (pin "1") (pinfunction "1_1") (pintype "passive"))
      (node (ref "R50") (pin "1") (pinfunction "1_1") (pintype "passive"))
      (node (ref "SW3") (pin "1") (pinfunction "0_1") (pintype "passive"))
      (node (ref "SW3") (pin "2") (pinfunction "0_2") (pintype "passive"))
    )
    (net (code "21") (name "Net-(D9-A)") (class "Default")
      (node (ref "D9") (pin "2") (pinfunction "A_2") (pintype "passive"))
      (node (ref "R20") (pin "2") (pinfunction "2_2") (pintype "passive"))
      (node (ref "T9") (pin "B") (pinfunction "B_B") (pintype "passive"))
      (node (ref "U6") (pin "2") (pinfunction "SWE_2") (pintype "input"))
    )
    (net (code "22") (name "Net-(D9-C)") (class "Default")
      (node (ref "D9") (pin "1") (pinfunction "C_1") (pintype "passive"))
      (node (ref "T8") (pin "1") (pinfunction "G_1") (pintype "passive"))
      (node (ref "T9") (pin "E") (pinfunction "E_E") (pintype "passive"))
    )
    (net (code "23") (name "Net-(D10-C)") (class "Default")
      (node (ref "D10") (pin "1") (pinfunction "C_1") (pintype "passive"))
      (node (ref "R30") (pin "1") (pinfunction "1_1") (pintype "passive"))
      (node (ref "T12") (pin "2") (pinfunction "S_2") (pintype "passive"))
      (node (ref "T4") (pin "2") (pinfunction "S_2") (pintype "passive"))
    )
    (net (code "24") (name "Net-(D11-A1)") (class "Default")
      (node (ref "D11") (pin "1") (pinfunction "A1_1") (pintype "passive"))
      (node (ref "R28") (pin "2") (pinfunction "2_2") (pintype "passive"))
      (node (ref "U2") (pin "18") (pinfunction "PB0_18") (pintype "bidirectional"))
    )
    (net (code "25") (name "Net-(D11-A2)") (class "Default")
      (node (ref "D11") (pin "2") (pinfunction "A2_2") (pintype "passive"))
      (node (ref "R30") (pin "2") (pinfunction "2_2") (pintype "passive"))
      (node (ref "T12") (pin "1") (pinfunction "G_1") (pintype "passive"))
      (node (ref "T13") (pin "3") (pinfunction "D_3") (pintype "passive"))
    )
    (net (code "26") (name "Net-(D11-C)") (class "Default")
      (node (ref "D11") (pin "3") (pinfunction "C_3") (pintype "passive"))
      (node (ref "SW6") (pin "3") (pinfunction "1_3") (pintype "passive"))
      (node (ref "SW6") (pin "4") (pinfunction "1_4") (pintype "passive"))
    )
    (net (code "27") (name "Net-(D12-A2)") (class "Default")
      (node (ref "D12") (pin "2") (pinfunction "A2_2") (pintype "passive"))
      (node (ref "SG1") (pin "1") (pinfunction "1_1") (pintype "passive"))
      (node (ref "T14") (pin "3") (pinfunction "C_3") (pintype "passive"))
    )
    (net (code "28") (name "Net-(LED1-PadA)") (class "Default")
      (node (ref "LED1") (pin "A") (pinfunction "A_A") (pintype "passive"))
      (node (ref "R37") (pin "1") (pinfunction "1_1") (pintype "passive"))
    )
    (net (code "29") (name "Net-(Q2-2)") (class "Default")
      (node (ref "C38") (pin "2") (pinfunction "2_2") (pintype "passive"))
      (node (ref "Q2") (pin "4") (pinfunction "2_4") (pintype "passive"))
      (node (ref "U2") (pin "3") (pinfunction "PC14-OSC32_IN_3") (pintype "bidirectional"))
    )
    (net (code "30") (name "Net-(R5-Pad1)") (class "Default")
      (node (ref "R5") (pin "1") (pinfunction "1_1") (pintype "passive"))
      (node (ref "R6") (pin "2") (pinfunction "2_2") (pintype "passive"))
    )
    (net (code "31") (name "Net-(R6-Pad1)") (class "Default")
      (node (ref "R6") (pin "1") (pinfunction "1_1") (pintype "passive"))
      (node (ref "R7") (pin "2") (pinfunction "2_2") (pintype "passive"))
    )
    (net (code "32") (name "Net-(R10-Pad2)") (class "Default")
      (node (ref "R10") (pin "2") (pinfunction "2_2") (pintype "passive"))
      (node (ref "R16") (pin "1") (pinfunction "1_1") (pintype "passive"))
      (node (ref "T18") (pin "B") (pinfunction "B_B") (pintype "passive"))
    )
    (net (code "33") (name "Net-(R13-Pad1)") (class "Default")
      (node (ref "R13") (pin "1") (pinfunction "1_1") (pintype "passive"))
      (node (ref "R14") (pin "2") (pinfunction "2_2") (pintype "passive"))
    )
    (net (code "34") (name "Net-(R14-Pad1)") (class "Default")
      (node (ref "R14") (pin "1") (pinfunction "1_1") (pintype "passive"))
      (node (ref "R15") (pin "2") (pinfunction "2_2") (pintype "passive"))
    )
    (net (code "35") (name "Net-(R18-Pad1)") (class "Default")
      (node (ref "R18") (pin "1") (pinfunction "1_1") (pintype "passive"))
      (node (ref "T18") (pin "C") (pinfunction "C_C") (pintype "passive"))
    )
    (net (code "36") (name "Net-(R33-Pad2)") (class "Default")
      (node (ref "R33") (pin "2") (pinfunction "2_2") (pintype "passive"))
      (node (ref "U$1") (pin "+") (pinfunction "+_+") (pintype "bidirectional"))
    )
    (net (code "37") (name "Net-(R39-Pad2)") (class "Default")
      (node (ref "R39") (pin "2") (pinfunction "2_2") (pintype "passive"))
      (node (ref "X1") (pin "2") (pinfunction "2_2") (pintype "passive"))
    )
    (net (code "38") (name "Net-(R40-Pad2)") (class "Default")
      (node (ref "R40") (pin "2") (pinfunction "2_2") (pintype "passive"))
      (node (ref "X1") (pin "3") (pinfunction "3_3") (pintype "passive"))
    )
    (net (code "39") (name "Net-(R42-Pad1)") (class "Default")
      (node (ref "R42") (pin "1") (pinfunction "1_1") (pintype "passive"))
      (node (ref "T15") (pin "B") (pinfunction "B_B") (pintype "passive"))
    )
    (net (code "40") (name "Net-(R44-Pad1)") (class "Default")
      (node (ref "R44") (pin "1") (pinfunction "1_1") (pintype "passive"))
      (node (ref "T15") (pin "C") (pinfunction "C_C") (pintype "passive"))
    )
    (net (code "41") (name "Net-(T1-G)") (class "Default")
      (node (ref "R2") (pin "1") (pinfunction "1_1") (pintype "passive"))
      (node (ref "T1") (pin "1") (pinfunction "G_1") (pintype "passive"))
      (node (ref "T2") (pin "3") (pinfunction "D_3") (pintype "passive"))
    )
    (net (code "42") (name "Net-(T1-S)") (class "Default")
      (node (ref "C2") (pin "1") (pinfunction "1_1") (pintype "passive"))
      (node (ref "R2") (pin "2") (pinfunction "2_2") (pintype "passive"))
      (node (ref "T1") (pin "2") (pinfunction "S_2") (pintype "passive"))
      (node (ref "U3") (pin "3") (pinfunction "VBAT_3") (pintype "output"))
    )
    (net (code "43") (name "Net-(T2-G)") (class "Default")
      (node (ref "R3") (pin "2") (pinfunction "2_2") (pintype "passive"))
      (node (ref "T2") (pin "1") (pinfunction "G_1") (pintype "passive"))
      (node (ref "U2") (pin "41") (pinfunction "PB5_41") (pintype "bidirectional"))
    )
    (net (code "44") (name "Net-(T3-G)") (class "Default")
      (node (ref "C3") (pin "2") (pinfunction "2_2") (pintype "passive"))
      (node (ref "R11") (pin "2") (pinfunction "2_2") (pintype "passive"))
      (node (ref "T3") (pin "1") (pinfunction "G_1") (pintype "passive"))
    )
    (net (code "45") (name "Net-(T5-D)") (class "Default")
      (node (ref "L1") (pin "1") (pinfunction "1_1") (pintype "passive"))
      (node (ref "T5") (pin "3") (pinfunction "D_3") (pintype "passive"))
    )
    (net (code "46") (name "Net-(T5-G)") (class "Default")
      (node (ref "R4") (pin "1") (pinfunction "1_1") (pintype "passive"))
      (node (ref "T5") (pin "1") (pinfunction "G_1") (pintype "passive"))
      (node (ref "T6") (pin "3") (pinfunction "D_3") (pintype "passive"))
    )
    (net (code "47") (name "Net-(T6-G)") (class "Default")
      (node (ref "R17") (pin "1") (pinfunction "1_1") (pintype "passive"))
      (node (ref "T6") (pin "1") (pinfunction "G_1") (pintype "passive"))
      (node (ref "U2") (pin "16") (pinfunction "PA6_16") (pintype "bidirectional"))
    )
    (net (code "48") (name "Net-(T7-B)") (class "Default")
      (node (ref "C15") (pin "1") (pinfunction "1_1") (pintype "passive"))
      (node (ref "R18") (pin "2") (pinfunction "2_2") (pintype "passive"))
      (node (ref "R19") (pin "2") (pinfunction "2_2") (pintype "passive"))
      (node (ref "T7") (pin "1") (pinfunction "B_1") (pintype "passive"))
    )
    (net (code "49") (name "Net-(T7-C)") (class "Default")
      (node (ref "R8") (pin "2") (pinfunction "2_2") (pintype "passive"))
      (node (ref "T7") (pin "3") (pinfunction "C_3") (pintype "passive"))
      (node (ref "U2") (pin "20") (pinfunction "PB2_20") (pintype "bidirectional"))
    )
    (net (code "50") (name "Net-(T8-D)") (class "Default")
      (node (ref "T8") (pin "3") (pinfunction "D_3") (pintype "passive"))
      (node (ref "TR1") (pin "1") (pinfunction "1_1") (pintype "bidirectional"))
    )
    (net (code "51") (name "Net-(T10-D)") (class "Default")
      (node (ref "R25") (pin "2") (pinfunction "2_2") (pintype "passive"))
      (node (ref "T10") (pin "3") (pinfunction "D_3") (pintype "passive"))
    )
    (net (code "52") (name "Net-(T10-G)") (class "Default")
      (node (ref "R23") (pin "2") (pinfunction "2_2") (pintype "passive"))
      (node (ref "T10") (pin "1") (pinfunction "G_1") (pintype "passive"))
      (node (ref "T11") (pin "3") (pinfunction "D_3") (pintype "passive"))
    )
    (net (code "53") (name "Net-(T10-S)") (class "Default")
      (node (ref "C3") (pin "1") (pinfunction "1_1") (pintype "passive"))
      (node (ref "C4") (pin "1") (pinfunction "1_1") (pintype "passive"))
      (node (ref "R23") (pin "1") (pinfunction "1_1") (pintype "passive"))
      (node (ref "T10") (pin "2") (pinfunction "S_2") (pintype "passive"))
      (node (ref "T3") (pin "2") (pinfunction "S_2") (pintype "passive"))
      (node (ref "T4") (pin "3") (pinfunction "D_3") (pintype "passive"))
    )
    (net (code "54") (name "Net-(T11-G)") (class "Default")
      (node (ref "R24") (pin "2") (pinfunction "2_2") (pintype "passive"))
      (node (ref "R27") (pin "1") (pinfunction "1_1") (pintype "passive"))
      (node (ref "T11") (pin "1") (pinfunction "G_1") (pintype "passive"))
    )
    (net (code "55") (name "Net-(T12-D)") (class "Default")
      (node (ref "L5") (pin "2") (pinfunction "2_2") (pintype "passive"))
      (node (ref "T12") (pin "3") (pinfunction "D_3") (pintype "passive"))
    )
    (net (code "56") (name "Net-(T13-G)") (class "Default")
      (node (ref "R31") (pin "2") (pinfunction "2_2") (pintype "passive"))
      (node (ref "T13") (pin "1") (pinfunction "G_1") (pintype "passive"))
      (node (ref "U2") (pin "19") (pinfunction "PB1_19") (pintype "bidirectional"))
    )
    (net (code "57") (name "Net-(T14-B)") (class "Default")
      (node (ref "R34") (pin "1") (pinfunction "1_1") (pintype "passive"))
      (node (ref "R35") (pin "1") (pinfunction "1_1") (pintype "passive"))
      (node (ref "T14") (pin "1") (pinfunction "B_1") (pintype "passive"))
    )
    (net (code "58") (name "Net-(T16-B)") (class "Default")
      (node (ref "R43") (pin "2") (pinfunction "2_2") (pintype "passive"))
      (node (ref "R45") (pin "2") (pinfunction "2_2") (pintype "passive"))
      (node (ref "T16") (pin "1") (pinfunction "B_1") (pintype "passive"))
    )
    (net (code "59") (name "Net-(T16-C)") (class "Default")
      (node (ref "R41") (pin "1") (pinfunction "1_1") (pintype "passive"))
      (node (ref "R42") (pin "2") (pinfunction "2_2") (pintype "passive"))
      (node (ref "T16") (pin "3") (pinfunction "C_3") (pintype "passive"))
    )
    (net (code "60") (name "Net-(U$5-CS)") (class "Default")
      (node (ref "U$5") (pin "1") (pinfunction "CS_1") (pintype "bidirectional"))
      (node (ref "U2") (pin "14") (pinfunction "PA4_14") (pintype "bidirectional"))
    )
    (net (code "61") (name "Net-(U$5-LEDA)") (class "Default")
      (node (ref "R44") (pin "2") (pinfunction "2_2") (pintype "passive"))
      (node (ref "U$5") (pin "8") (pinfunction "LEDA_8") (pintype "bidirectional"))
    )
    (net (code "62") (name "Net-(U$5-RES)") (class "Default")
      (node (ref "U$5") (pin "2") (pinfunction "RES_2") (pintype "bidirectional"))
      (node (ref "U2") (pin "2") (pinfunction "PC13-TAMPER-RTC_2") (pintype "bidirectional"))
    )
    (net (code "63") (name "Net-(U$5-RS)") (class "Default")
      (node (ref "U$5") (pin "3") (pinfunction "RS_3") (pintype "bidirectional"))
      (node (ref "U2") (pin "42") (pinfunction "PB6_42") (pintype "bidirectional"))
    )
    (net (code "64") (name "Net-(U$5-SCK)") (class "Default")
      (node (ref "U$5") (pin "4") (pinfunction "SCK_4") (pintype "bidirectional"))
      (node (ref "U2") (pin "17") (pinfunction "PA7_17") (pintype "bidirectional"))
    )
    (net (code "65") (name "Net-(U$5-SI)") (class "Default")
      (node (ref "U$5") (pin "5") (pinfunction "SI_5") (pintype "bidirectional"))
      (node (ref "U2") (pin "15") (pinfunction "PA5_15") (pintype "bidirectional"))
    )
    (net (code "66") (name "Net-(U1-C)") (class "Default")
      (node (ref "U1") (pin "6") (pinfunction "C_6") (pintype "input"))
      (node (ref "U2") (pin "26") (pinfunction "PB13_26") (pintype "bidirectional"))
    )
    (net (code "67") (name "Net-(U1-D)") (class "Default")
      (node (ref "U1") (pin "5") (pinfunction "D_5") (pintype "input"))
      (node (ref "U2") (pin "28") (pinfunction "PB15_28") (pintype "bidirectional"))
    )
    (net (code "68") (name "Net-(U1-Q)") (class "Default")
      (node (ref "U1") (pin "2") (pinfunction "Q_2") (pintype "output"))
      (node (ref "U2") (pin "27") (pinfunction "PB14_27") (pintype "bidirectional"))
    )
    (net (code "69") (name "Net-(U1-~{S})") (class "Default")
      (node (ref "U1") (pin "1") (pinfunction "~{S}_1") (pintype "input"))
      (node (ref "U2") (pin "25") (pinfunction "PB12_25") (pintype "bidirectional"))
    )
    (net (code "70") (name "Net-(U2-BOOT0)") (class "Default")
      (node (ref "JP3") (pin "1") (pinfunction "1_1") (pintype "passive"))
      (node (ref "R36") (pin "2") (pinfunction "2_2") (pintype "passive"))
      (node (ref "U2") (pin "44") (pinfunction "BOOT0_44") (pintype "input"))
    )
    (net (code "71") (name "Net-(U2-NRST)") (class "Default")
      (node (ref "C36") (pin "1") (pinfunction "1_1") (pintype "passive"))
      (node (ref "U2") (pin "7") (pinfunction "NRST_7") (pintype "input"))
    )
    (net (code "72") (name "Net-(U2-PA0_WKUP)") (class "Default")
      (node (ref "C27") (pin "1") (pinfunction "1_1") (pintype "passive"))
      (node (ref "R25") (pin "1") (pinfunction "1_1") (pintype "passive"))
      (node (ref "R26") (pin "2") (pinfunction "2_2") (pintype "passive"))
      (node (ref "U2") (pin "10") (pinfunction "PA0_WKUP_10") (pintype "bidirectional"))
    )
    (net (code "73") (name "Net-(U2-PA1)") (class "Default")
      (node (ref "C26") (pin "1") (pinfunction "1_1") (pintype "passive"))
      (node (ref "R29") (pin "1") (pinfunction "1_1") (pintype "passive"))
      (node (ref "R32") (pin "2") (pinfunction "2_2") (pintype "passive"))
      (node (ref "U2") (pin "11") (pinfunction "PA1_11") (pintype "bidirectional"))
    )
    (net (code "74") (name "Net-(U2-PA2)") (class "Default")
      (node (ref "JP1") (pin "3") (pinfunction "3_3") (pintype "passive"))
      (node (ref "U2") (pin "12") (pinfunction "PA2_12") (pintype "bidirectional"))
    )
    (net (code "75") (name "Net-(U2-PA3)") (class "Default")
      (node (ref "JP1") (pin "2") (pinfunction "2_2") (pintype "passive"))
      (node (ref "U2") (pin "13") (pinfunction "PA3_13") (pintype "bidirectional"))
    )
    (net (code "76") (name "Net-(U2-PA8)") (class "Default")
      (node (ref "R34") (pin "2") (pinfunction "2_2") (pintype "passive"))
      (node (ref "U2") (pin "29") (pinfunction "PA8_29") (pintype "bidirectional"))
    )
    (net (code "77") (name "Net-(U2-PA9)") (class "Default")
      (node (ref "JP6") (pin "3") (pinfunction "3_3") (pintype "passive"))
      (node (ref "U2") (pin "30") (pinfunction "PA9_30") (pintype "bidirectional"))
    )
    (net (code "78") (name "Net-(U2-PA10)") (class "Default")
      (node (ref "JP6") (pin "2") (pinfunction "2_2") (pintype "passive"))
      (node (ref "U2") (pin "31") (pinfunction "PA10_31") (pintype "bidirectional"))
    )
    (net (code "79") (name "Net-(U2-PA11)") (class "Default")
      (node (ref "R39") (pin "1") (pinfunction "1_1") (pintype "passive"))
      (node (ref "U2") (pin "32") (pinfunction "PA11_32") (pintype "bidirectional"))
    )
    (net (code "80") (name "Net-(U2-PA12)") (class "Default")
      (node (ref "R40") (pin "1") (pinfunction "1_1") (pintype "passive"))
      (node (ref "U2") (pin "33") (pinfunction "PA12_33") (pintype "bidirectional"))
    )
    (net (code "81") (name "Net-(U2-PA13)") (class "Default")
      (node (ref "JP7") (pin "5") (pinfunction "5_5") (pintype "passive"))
      (node (ref "U2") (pin "34") (pinfunction "PA13_34") (pintype "bidirectional"))
    )
    (net (code "82") (name "Net-(U2-PA14)") (class "Default")
      (node (ref "JP7") (pin "4") (pinfunction "4_4") (pintype "passive"))
      (node (ref "U2") (pin "37") (pinfunction "PA14_37") (pintype "bidirectional"))
    )
    (net (code "83") (name "Net-(U2-PA15)") (class "Default")
      (node (ref "R43") (pin "1") (pinfunction "1_1") (pintype "passive"))
      (node (ref "U2") (pin "38") (pinfunction "PA15_38") (pintype "bidirectional"))
    )
    (net (code "84") (name "Net-(U2-PB3)") (class "Default")
      (node (ref "JP7") (pin "3") (pinfunction "3_3") (pintype "passive"))
      (node (ref "U2") (pin "39") (pinfunction "PB3_39") (pintype "bidirectional"))
    )
    (net (code "85") (name "Net-(U2-PB4)") (class "Default")
      (node (ref "R37") (pin "2") (pinfunction "2_2") (pintype "passive"))
      (node (ref "U2") (pin "40") (pinfunction "PB4_40") (pintype "bidirectional"))
    )
    (net (code "86") (name "Net-(U2-PB7)") (class "Default")
      (node (ref "R46") (pin "2") (pinfunction "2_2") (pintype "passive"))
      (node (ref "R51") (pin "2") (pinfunction "2_2") (pintype "passive"))
      (node (ref "U2") (pin "43") (pinfunction "PB7_43") (pintype "bidirectional"))
    )
    (net (code "87") (name "Net-(U2-PB8)") (class "Default")
      (node (ref "R47") (pin "2") (pinfunction "2_2") (pintype "passive"))
      (node (ref "R52") (pin "2") (pinfunction "2_2") (pintype "passive"))
      (node (ref "U2") (pin "45") (pinfunction "PB8_45") (pintype "bidirectional"))
    )
    (net (code "88") (name "Net-(U2-PB9)") (class "Default")
      (node (ref "R48") (pin "2") (pinfunction "2_2") (pintype "passive"))
      (node (ref "R53") (pin "2") (pinfunction "2_2") (pintype "passive"))
      (node (ref "U2") (pin "46") (pinfunction "PB9_46") (pintype "bidirectional"))
    )
    (net (code "89") (name "Net-(U2-PB10)") (class "Default")
      (node (ref "R49") (pin "2") (pinfunction "2_2") (pintype "passive"))
      (node (ref "R54") (pin "2") (pinfunction "2_2") (pintype "passive"))
      (node (ref "U2") (pin "21") (pinfunction "PB10_21") (pintype "bidirectional"))
    )
    (net (code "90") (name "Net-(U2-PB11)") (class "Default")
      (node (ref "R50") (pin "2") (pinfunction "2_2") (pintype "passive"))
      (node (ref "R55") (pin "2") (pinfunction "2_2") (pintype "passive"))
      (node (ref "U2") (pin "22") (pinfunction "PB11_22") (pintype "bidirectional"))
    )
    (net (code "91") (name "Net-(U2-PC15-OSC32_OUT)") (class "Default")
      (node (ref "C40") (pin "2") (pinfunction "2_2") (pintype "passive"))
      (node (ref "Q2") (pin "1") (pinfunction "1_1") (pintype "passive"))
      (node (ref "U2") (pin "4") (pinfunction "PC15-OSC32_OUT_4") (pintype "bidirectional"))
    )
    (net (code "92") (name "Net-(U2-PD0_OSC_IN)") (class "Default")
      (node (ref "C37") (pin "1") (pinfunction "1_1") (pintype "passive"))
      (node (ref "Q1") (pin "2") (pinfunction "2_2") (pintype "passive"))
      (node (ref "U2") (pin "5") (pinfunction "PD0_OSC_IN_5") (pintype "bidirectional"))
    )
    (net (code "93") (name "Net-(U2-PD1_OSC_OUT)") (class "Default")
      (node (ref "C41") (pin "1") (pinfunction "1_1") (pintype "passive"))
      (node (ref "Q1") (pin "1") (pinfunction "1_1") (pintype "passive"))
      (node (ref "U2") (pin "6") (pinfunction "PD1_OSC_OUT_6") (pintype "bidirectional"))
    )
    (net (code "94") (name "Net-(U2-VBAT)") (class "Default")
      (node (ref "C29") (pin "1") (pinfunction "1_1") (pintype "passive"))
      (node (ref "R33") (pin "1") (pinfunction "1_1") (pintype "passive"))
      (node (ref "U2") (pin "1") (pinfunction "VBAT_1") (pintype "bidirectional"))
    )
    (net (code "95") (name "Net-(U2-VDDA)") (class "Default")
      (node (ref "C34") (pin "1") (pinfunction "1_1") (pintype "passive"))
      (node (ref "C35") (pin "1") (pinfunction "1_1") (pintype "passive"))
      (node (ref "L4") (pin "1") (pinfunction "1_1") (pintype "passive"))
      (node (ref "U2") (pin "9") (pinfunction "VDDA_9") (pintype "power_in"))
    )
    (net (code "96") (name "Net-(U3-PROG)") (class "Default")
      (node (ref "R1") (pin "2") (pinfunction "2_2") (pintype "passive"))
      (node (ref "U3") (pin "5") (pinfunction "PROG_5") (pintype "input"))
    )
    (net (code "97") (name "Net-(U5-LX)") (class "Default")
      (node (ref "L2") (pin "1") (pinfunction "1_1") (pintype "passive"))
      (node (ref "U5") (pin "7") (pinfunction "LX_7") (pintype "bidirectional"))
    )
    (net (code "98") (name "Net-(U5-REF)") (class "Default")
      (node (ref "C23") (pin "1") (pinfunction "1_1") (pintype "passive"))
      (node (ref "U5") (pin "4") (pinfunction "REF_4") (pintype "bidirectional"))
    )
    (net (code "99") (name "Net-(U6-COMP)") (class "Default")
      (node (ref "C18") (pin "1") (pinfunction "1_1") (pintype "passive"))
      (node (ref "R21") (pin "2") (pinfunction "2_2") (pintype "passive"))
      (node (ref "R5") (pin "2") (pinfunction "2_2") (pintype "passive"))
      (node (ref "U6") (pin "5") (pinfunction "COMP_5") (pintype "input"))
    )
    (net (code "100") (name "Net-(U6-DC)") (class "Default")
      (node (ref "C10") (pin "+") (pinfunction "+_+") (pintype "passive"))
      (node (ref "C11") (pin "1") (pinfunction "1_1") (pintype "passive"))
      (node (ref "L1") (pin "2") (pinfunction "2_2") (pintype "passive"))
      (node (ref "R12") (pin "1") (pinfunction "1_1") (pintype "passive"))
      (node (ref "R9") (pin "1") (pinfunction "1_1") (pintype "passive"))
      (node (ref "U6") (pin "1") (pinfunction "SWC_1") (pintype "input"))
      (node (ref "U6") (pin "6") (pinfunction "VCC_6") (pintype "power_in"))
      (node (ref "U6") (pin "8") (pinfunction "DC_8") (pintype "input"))
    )
    (net (code "101") (name "Net-(U6-IPK)") (class "Default")
      (node (ref "C9") (pin "+") (pinfunction "+_+") (pintype "passive"))
      (node (ref "R12") (pin "2") (pinfunction "2_2") (pintype "passive"))
      (node (ref "R9") (pin "2") (pinfunction "2_2") (pintype "passive"))
      (node (ref "TR1") (pin "2") (pinfunction "2_2") (pintype "bidirectional"))
      (node (ref "U6") (pin "7") (pinfunction "IPK_7") (pintype "bidirectional"))
    )
    (net (code "102") (name "Net-(U6-TC)") (class "Default")
      (node (ref "C19") (pin "1") (pinfunction "1_1") (pintype "passive"))
      (node (ref "U6") (pin "3") (pinfunction "TC_3") (pintype "input"))
    )
    (net (code "103") (name "unconnected-(D12-A1-Pad1)") (class "Default")
      (node (ref "D12") (pin "1") (pinfunction "A1_1") (pintype "passive"))
    )
    (net (code "104") (name "unconnected-(U$5-IC_CS-Pad11)") (class "Default")
      (node (ref "U$5") (pin "11") (pinfunction "IC_CS_11") (pintype "bidirectional"))
    )
    (net (code "105") (name "unconnected-(U$5-IC_SCK-Pad10)") (class "Default")
      (node (ref "U$5") (pin "10") (pinfunction "IC_SCK_10") (pintype "bidirectional"))
    )
    (net (code "106") (name "unconnected-(U$5-IC_SDI-Pad13)") (class "Default")
      (node (ref "U$5") (pin "13") (pinfunction "IC_SDI_13") (pintype "bidirectional"))
    )
    (net (code "107") (name "unconnected-(U$5-IC_SDO-Pad12)") (class "Default")
      (node (ref "U$5") (pin "12") (pinfunction "IC_SDO_12") (pintype "bidirectional"))
    )
    (net (code "108") (name "unconnected-(U3-STAT-Pad1)") (class "Default")
      (node (ref "U3") (pin "1") (pinfunction "STAT_1") (pintype "output"))
    )
    (net (code "109") (name "unconnected-(U5-LBI-Pad2)") (class "Default")
      (node (ref "U5") (pin "2") (pinfunction "LBI_2") (pintype "bidirectional"))
    )
    (net (code "110") (name "unconnected-(U5-LBO-Pad3)") (class "Default")
      (node (ref "U5") (pin "3") (pinfunction "LBO_3") (pintype "bidirectional"))
    )
    (net (code "111") (name "unconnected-(U5-SHDN-Pad5)") (class "Default")
      (node (ref "U5") (pin "5") (pinfunction "SHDN_5") (pintype "bidirectional"))
    )
  )
)
